# day_1.net
KiCad netlist of a schematic drawn in EAGLE
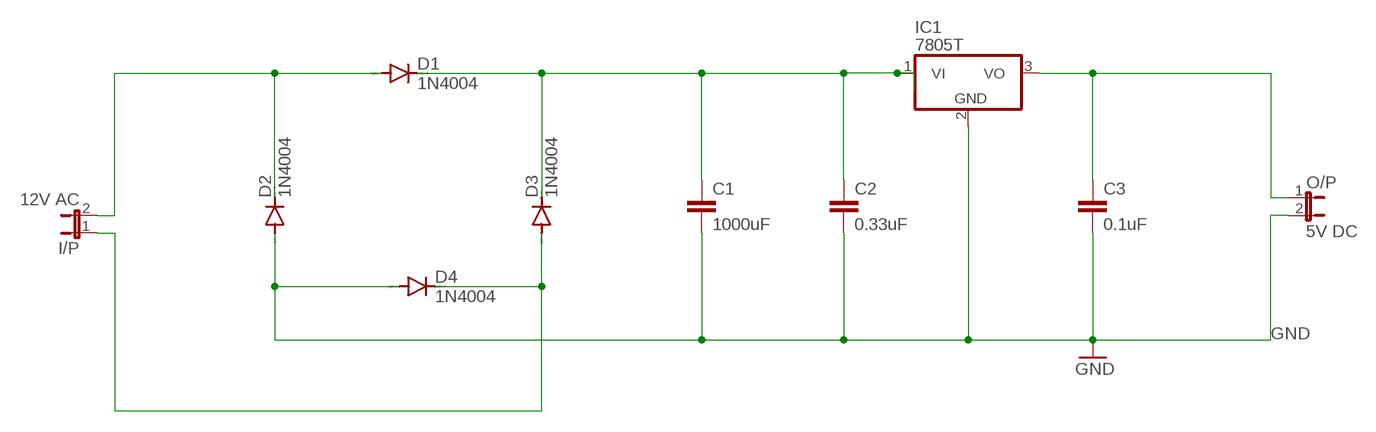
[diagram p0: schematic, sheet 1]

(export (version "E")
  (design (tool "Eeschema 10.0.6"))
  (components
    (comp (ref "C1")
      (value "1000uF")
      (footprint "eagle-import:C2.5-3")
      (libsource (lib "eagle-import") (part "C2,5-3"))
    )
    (comp (ref "C2")
      (value "0.33uF")
      (footprint "eagle-import:C2.5-3")
      (libsource (lib "eagle-import") (part "C2,5-3"))
    )
    (comp (ref "C3")
      (value "0.1uF")
      (footprint "eagle-import:C2.5-3")
      (libsource (lib "eagle-import") (part "C2,5-3"))
    )
    (comp (ref "D1")
      (value "1N4004")
      (footprint "eagle-import:DO41-10")
      (libsource (lib "eagle-import") (part "1N4004"))
    )
    (comp (ref "D2")
      (value "1N4004")
      (footprint "eagle-import:DO41-10")
      (libsource (lib "eagle-import") (part "1N4004"))
    )
    (comp (ref "D3")
      (value "1N4004")
      (footprint "eagle-import:DO41-10")
      (libsource (lib "eagle-import") (part "1N4004"))
    )
    (comp (ref "D4")
      (value "1N4004")
      (footprint "eagle-import:DO41-10")
      (libsource (lib "eagle-import") (part "1N4004"))
    )
    (comp (ref "I/P")
      (value "12V AC")
      (footprint "eagle-import:JP1")
      (libsource (lib "eagle-import") (part "JP1E"))
    )
    (comp (ref "IC1")
      (value "7805T")
      (footprint "eagle-import:TO220H")
      (libsource (lib "eagle-import") (part "78T05"))
    )
    (comp (ref "O/P")
      (value "5V DC")
      (footprint "eagle-import:JP1")
      (libsource (lib "eagle-import") (part "JP1E"))
    )
  )
  (nets
    (net (code "1") (name "GND") (class "Default")
      (node (ref "C1") (pin "2") (pinfunction "2_2") (pintype "passive"))
      (node (ref "C2") (pin "2") (pinfunction "2_2") (pintype "passive"))
      (node (ref "C3") (pin "2") (pinfunction "2_2") (pintype "passive"))
      (node (ref "D2") (pin "A") (pinfunction "A_A") (pintype "passive"))
      (node (ref "D4") (pin "A") (pinfunction "A_A") (pintype "passive"))
      (node (ref "IC1") (pin "2") (pinfunction "GND_2") (pintype "passive"))
      (node (ref "O/P") (pin "2") (pinfunction "2_2") (pintype "passive"))
    )
    (net (code "2") (name "Net-(D1-PadA)") (class "Default")
      (node (ref "D1") (pin "A") (pinfunction "A_A") (pintype "passive"))
      (node (ref "D2") (pin "C") (pinfunction "C_C") (pintype "passive"))
      (node (ref "I/P") (pin "2") (pinfunction "2_2") (pintype "passive"))
    )
    (net (code "3") (name "Net-(D3-PadA)") (class "Default")
      (node (ref "D3") (pin "A") (pinfunction "A_A") (pintype "passive"))
      (node (ref "D4") (pin "C") (pinfunction "C_C") (pintype "passive"))
      (node (ref "I/P") (pin "1") (pinfunction "1_1") (pintype "passive"))
    )
    (net (code "4") (name "Net-(IC1-VI)") (class "Default")
      (node (ref "C1") (pin "1") (pinfunction "1_1") (pintype "passive"))
      (node (ref "C2") (pin "1") (pinfunction "1_1") (pintype "passive"))
      (node (ref "D1") (pin "C") (pinfunction "C_C") (pintype "passive"))
      (node (ref "D3") (pin "C") (pinfunction "C_C") (pintype "passive"))
      (node (ref "IC1") (pin "1") (pinfunction "VI_1") (pintype "input"))
    )
    (net (code "5") (name "Net-(IC1-VO)") (class "Default")
      (node (ref "C3") (pin "1") (pinfunction "1_1") (pintype "passive"))
      (node (ref "IC1") (pin "3") (pinfunction "VO_3") (pintype "passive"))
      (node (ref "O/P") (pin "1") (pinfunction "1_1") (pintype "passive"))
    )
  )
)
